# Kaiwa_vox_1_0.net
KiCad netlist of a schematic drawn in EAGLE
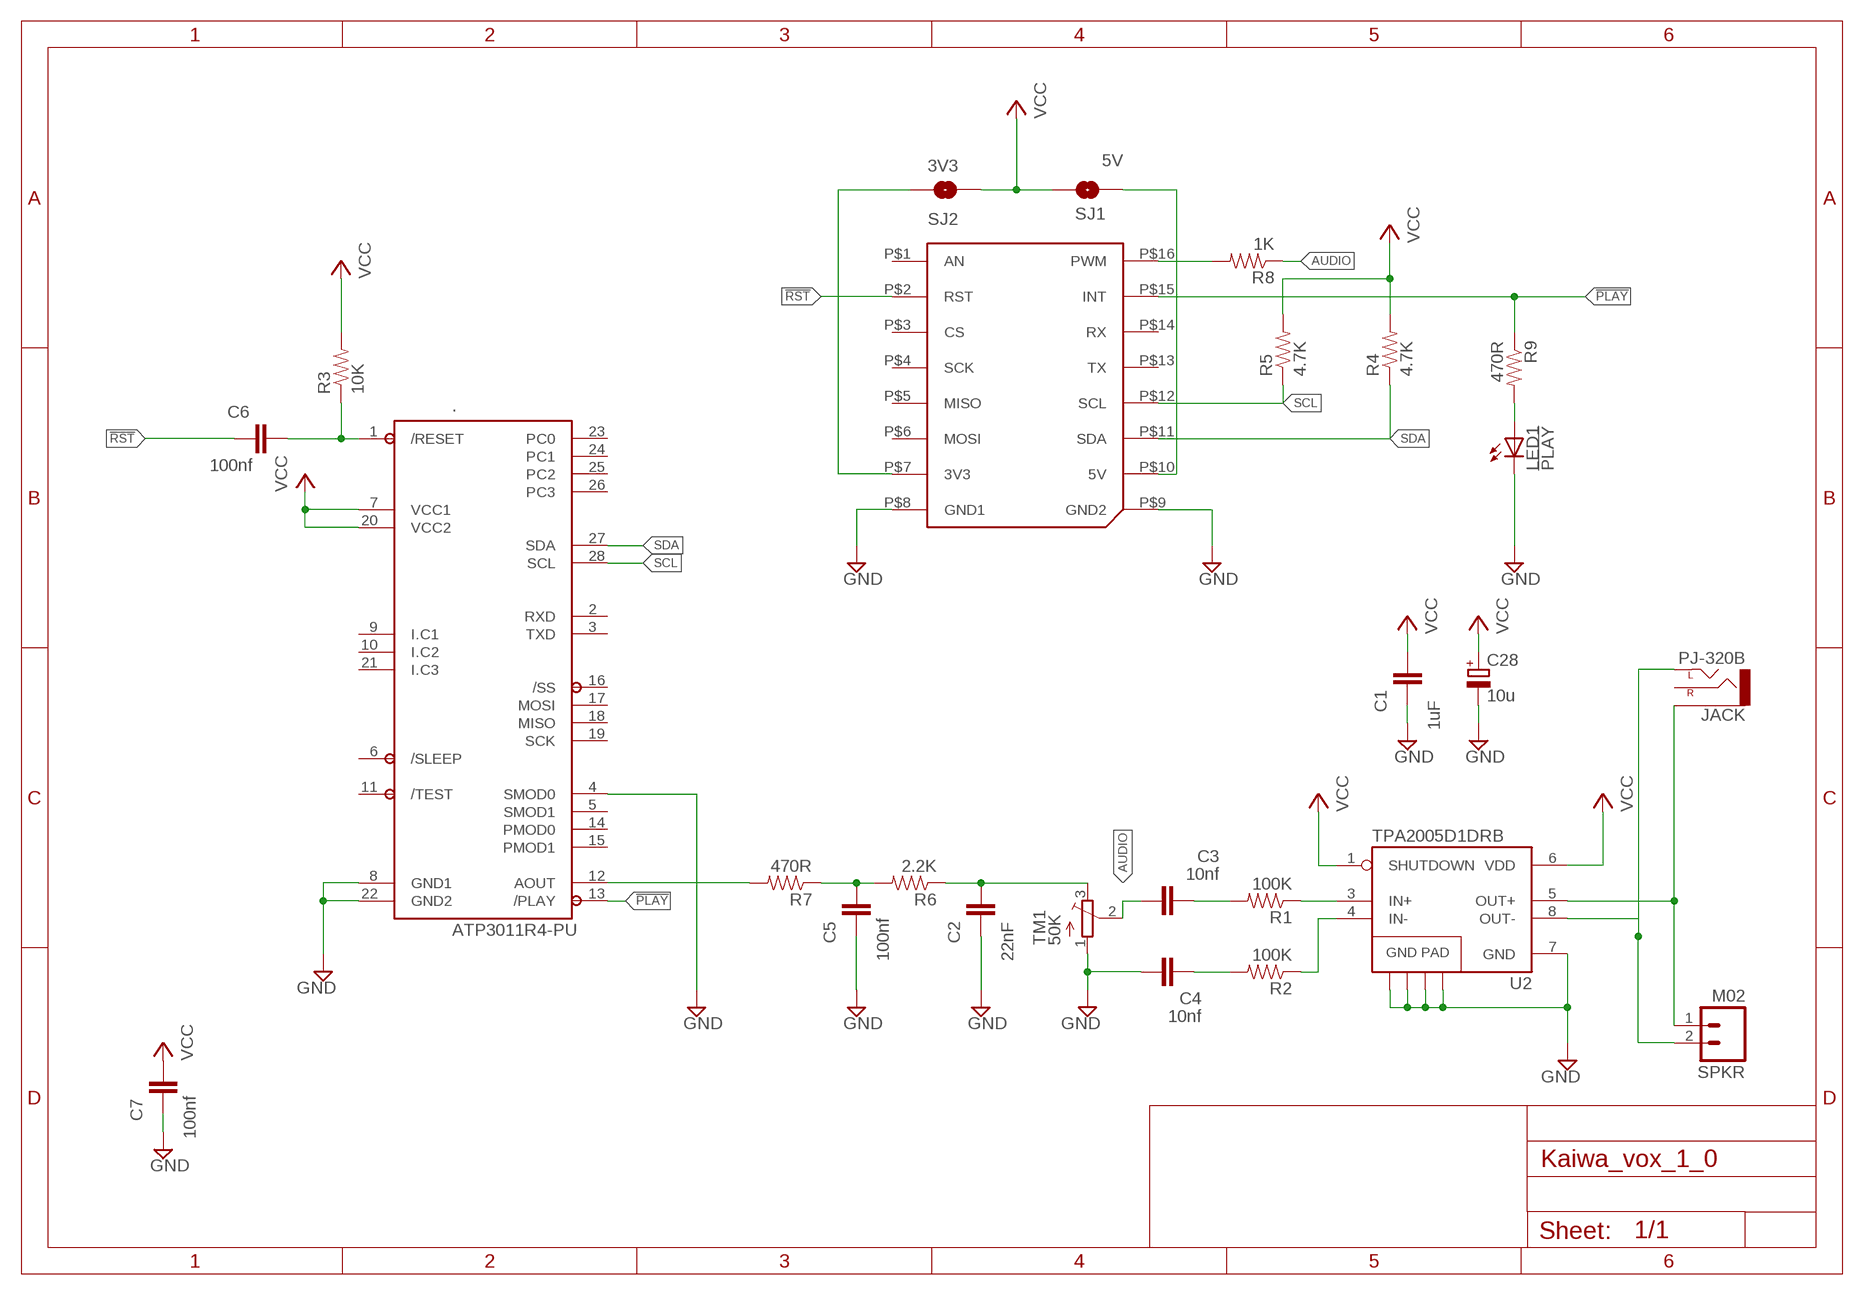
[diagram p0: schematic, sheet 1]

(export (version "E")
  (design (tool "Eeschema 10.0.6"))
  (components
    (comp (ref ".")
      (value "ATP3011R4-PU")
      (footprint "eagle-import:DIP28")
      (libsource (lib "eagle-import") (part "ATMEGA328"))
    )
    (comp (ref "C1")
      (value "1uF")
      (footprint "eagle-import:SPARKFUN_0805")
      (libsource (lib "eagle-import") (part "SPARKFUN_CAP0805"))
    )
    (comp (ref "C2")
      (value "22nF")
      (footprint "eagle-import:SPARKFUN_0805")
      (libsource (lib "eagle-import") (part "SPARKFUN_CAP0805"))
    )
    (comp (ref "C3")
      (value "10nf")
      (footprint "eagle-import:SPARKFUN_0805")
      (libsource (lib "eagle-import") (part "SPARKFUN_CAP0805"))
    )
    (comp (ref "C4")
      (value "10nf")
      (footprint "eagle-import:SPARKFUN_0805")
      (libsource (lib "eagle-import") (part "SPARKFUN_CAP0805"))
    )
    (comp (ref "C5")
      (value "100nf")
      (footprint "eagle-import:SPARKFUN_0805")
      (libsource (lib "eagle-import") (part "SPARKFUN_CAP0805"))
    )
    (comp (ref "C6")
      (value "100nf")
      (footprint "eagle-import:SPARKFUN_0805")
      (libsource (lib "eagle-import") (part "SPARKFUN_CAP0805"))
    )
    (comp (ref "C7")
      (value "100nf")
      (footprint "eagle-import:SPARKFUN_0805")
      (libsource (lib "eagle-import") (part "SPARKFUN_CAP0805"))
    )
    (comp (ref "C28")
      (value "10u")
      (footprint "eagle-import:A_3216-18R")
      (libsource (lib "eagle-import") (part "CPOL-EUA/3216-18R"))
    )
    (comp (ref "CLICK")
      (value "MIKROE_CLICKLARGE")
      (footprint "eagle-import:MIKROE_BUS_LARGE")
      (libsource (lib "eagle-import") (part "MIKROE_CLICKLARGE"))
    )
    (comp (ref "JACK")
      (value "PJ-320B")
      (footprint "eagle-import:FOOTPRINT")
      (libsource (lib "eagle-import") (part "PJ-320B"))
    )
    (comp (ref "LED1")
      (value "!PLAY")
      (footprint "eagle-import:SML0603")
      (libsource (lib "eagle-import") (part "LEDSML0603"))
    )
    (comp (ref "R1")
      (value "100K")
      (footprint "eagle-import:SPARKFUN_0805")
      (libsource (lib "eagle-import") (part "SPARKFUN_RESISTOR0805-RES"))
    )
    (comp (ref "R2")
      (value "100K")
      (footprint "eagle-import:SPARKFUN_0805")
      (libsource (lib "eagle-import") (part "SPARKFUN_RESISTOR0805-RES"))
    )
    (comp (ref "R3")
      (value "10K")
      (footprint "eagle-import:SPARKFUN_0805")
      (libsource (lib "eagle-import") (part "SPARKFUN_RESISTOR0805-RES"))
    )
    (comp (ref "R4")
      (value "4.7K")
      (footprint "eagle-import:SPARKFUN_0805")
      (libsource (lib "eagle-import") (part "SPARKFUN_RESISTOR0805-RES"))
    )
    (comp (ref "R5")
      (value "4.7K")
      (footprint "eagle-import:SPARKFUN_0805")
      (libsource (lib "eagle-import") (part "SPARKFUN_RESISTOR0805-RES"))
    )
    (comp (ref "R6")
      (value "2.2K")
      (footprint "eagle-import:SPARKFUN_0805")
      (libsource (lib "eagle-import") (part "SPARKFUN_RESISTOR0805-RES"))
    )
    (comp (ref "R7")
      (value "470R")
      (footprint "eagle-import:SPARKFUN_0805")
      (libsource (lib "eagle-import") (part "SPARKFUN_RESISTOR0805-RES"))
    )
    (comp (ref "R8")
      (value "1K")
      (footprint "eagle-import:SPARKFUN_0805")
      (libsource (lib "eagle-import") (part "SPARKFUN_RESISTOR0805-RES"))
    )
    (comp (ref "R9")
      (value "470R")
      (footprint "eagle-import:SPARKFUN_0805")
      (libsource (lib "eagle-import") (part "SPARKFUN_RESISTOR0805-RES"))
    )
    (comp (ref "SJ1")
      (value "5V")
      (footprint "eagle-import:SPARKFUN_SJ_2S-TRACE")
      (libsource (lib "eagle-import") (part "SPARKFUN_SOLDERJUMPERTRACE"))
    )
    (comp (ref "SJ2")
      (value "3V3")
      (footprint "eagle-import:SPARKFUN_SJ_2S-NO")
      (libsource (lib "eagle-import") (part "SPARKFUN_SOLDERJUMPERNO"))
    )
    (comp (ref "SPKR")
      (value "M02")
      (footprint "eagle-import:1X02_LOCK_LONGPADS")
      (libsource (lib "eagle-import") (part "M02LOCK_LONGPADS"))
    )
    (comp (ref "TM1")
      (value "50K")
      (footprint "eagle-import:TC33X")
      (libsource (lib "eagle-import") (part "TRIMPOTTC33X"))
    )
    (comp (ref "U2")
      (value "TPA2005D1DRB")
      (footprint "eagle-import:QFN-8_PAD")
      (libsource (lib "eagle-import") (part "TPA2005D1DRB"))
    )
  )
  (nets
    (net (code "1") (name "/~{PLAY}") (class "Default")
      (node (ref ".") (pin "13") (pinfunction "/PLAY_13") (pintype "bidirectional"))
      (node (ref "CLICK") (pin "P$15") (pinfunction "INT_P$15") (pintype "bidirectional"))
      (node (ref "R9") (pin "1") (pinfunction "1_1") (pintype "passive"))
    )
    (net (code "2") (name "/~{RST}") (class "Default")
      (node (ref "C6") (pin "2") (pinfunction "2_2") (pintype "passive"))
      (node (ref "CLICK") (pin "P$2") (pinfunction "RST_P$2") (pintype "bidirectional"))
    )
    (net (code "3") (name "AUDIO") (class "Default")
      (node (ref "C3") (pin "1") (pinfunction "1_1") (pintype "passive"))
      (node (ref "R8") (pin "1") (pinfunction "1_1") (pintype "passive"))
      (node (ref "TM1") (pin "2") (pinfunction "S_2") (pintype "passive"))
    )
    (net (code "4") (name "GND") (class "Default")
      (node (ref ".") (pin "22") (pinfunction "GND2_22") (pintype "bidirectional"))
      (node (ref ".") (pin "4") (pinfunction "SMOD0_4") (pintype "bidirectional"))
      (node (ref ".") (pin "8") (pinfunction "GND1_8") (pintype "bidirectional"))
      (node (ref "C1") (pin "2") (pinfunction "2_2") (pintype "passive"))
      (node (ref "C2") (pin "2") (pinfunction "2_2") (pintype "passive"))
      (node (ref "C28") (pin "-") (pinfunction "-_-") (pintype "passive"))
      (node (ref "C4") (pin "1") (pinfunction "1_1") (pintype "passive"))
      (node (ref "C5") (pin "2") (pinfunction "2_2") (pintype "passive"))
      (node (ref "C7") (pin "2") (pinfunction "2_2") (pintype "passive"))
      (node (ref "CLICK") (pin "P$8") (pinfunction "GND1_P$8") (pintype "bidirectional"))
      (node (ref "CLICK") (pin "P$9") (pinfunction "GND2_P$9") (pintype "bidirectional"))
      (node (ref "LED1") (pin "C") (pinfunction "C_C") (pintype "passive"))
      (node (ref "TM1") (pin "1") (pinfunction "A_1") (pintype "passive"))
      (node (ref "U2") (pin "10") (pinfunction "GND_10") (pintype "power_in"))
      (node (ref "U2") (pin "11") (pinfunction "GND_11") (pintype "power_in"))
      (node (ref "U2") (pin "12") (pinfunction "GND_12") (pintype "bidirectional"))
      (node (ref "U2") (pin "13") (pinfunction "GND_13") (pintype "bidirectional"))
      (node (ref "U2") (pin "7") (pinfunction "GND_7") (pintype "power_in"))
    )
    (net (code "5") (name "Net-(.-AOUT)") (class "Default")
      (node (ref ".") (pin "12") (pinfunction "AOUT_12") (pintype "bidirectional"))
      (node (ref "R7") (pin "2") (pinfunction "2_2") (pintype "passive"))
    )
    (net (code "6") (name "Net-(.-{slash}RESET)") (class "Default")
      (node (ref ".") (pin "1") (pinfunction "/RESET_1") (pintype "bidirectional"))
      (node (ref "C6") (pin "1") (pinfunction "1_1") (pintype "passive"))
      (node (ref "R3") (pin "1") (pinfunction "1_1") (pintype "passive"))
    )
    (net (code "7") (name "Net-(C3-Pad2)") (class "Default")
      (node (ref "C3") (pin "2") (pinfunction "2_2") (pintype "passive"))
      (node (ref "R1") (pin "2") (pinfunction "2_2") (pintype "passive"))
    )
    (net (code "8") (name "Net-(C4-Pad2)") (class "Default")
      (node (ref "C4") (pin "2") (pinfunction "2_2") (pintype "passive"))
      (node (ref "R2") (pin "2") (pinfunction "2_2") (pintype "passive"))
    )
    (net (code "9") (name "Net-(C5-Pad1)") (class "Default")
      (node (ref "C5") (pin "1") (pinfunction "1_1") (pintype "passive"))
      (node (ref "R6") (pin "2") (pinfunction "2_2") (pintype "passive"))
      (node (ref "R7") (pin "1") (pinfunction "1_1") (pintype "passive"))
    )
    (net (code "10") (name "Net-(CLICK-3V3)") (class "Default")
      (node (ref "CLICK") (pin "P$7") (pinfunction "3V3_P$7") (pintype "bidirectional"))
      (node (ref "SJ2") (pin "1") (pinfunction "1_1") (pintype "passive"))
    )
    (net (code "11") (name "Net-(CLICK-5V)") (class "Default")
      (node (ref "CLICK") (pin "P$10") (pinfunction "5V_P$10") (pintype "bidirectional"))
      (node (ref "SJ1") (pin "1") (pinfunction "1_1") (pintype "passive"))
    )
    (net (code "12") (name "Net-(CLICK-PWM)") (class "Default")
      (node (ref "CLICK") (pin "P$16") (pinfunction "PWM_P$16") (pintype "bidirectional"))
      (node (ref "R8") (pin "2") (pinfunction "2_2") (pintype "passive"))
    )
    (net (code "13") (name "Net-(JACK-LEFT)") (class "Default")
      (node (ref "JACK") (pin "2") (pinfunction "LEFT_2") (pintype "bidirectional"))
      (node (ref "SPKR") (pin "2") (pinfunction "2_2") (pintype "passive"))
      (node (ref "U2") (pin "8") (pinfunction "OUT-_8") (pintype "bidirectional"))
    )
    (net (code "14") (name "Net-(JACK-SLEEVE)") (class "Default")
      (node (ref "JACK") (pin "4") (pinfunction "SLEEVE_4") (pintype "bidirectional"))
      (node (ref "SPKR") (pin "1") (pinfunction "1_1") (pintype "passive"))
      (node (ref "U2") (pin "5") (pinfunction "OUT+_5") (pintype "bidirectional"))
    )
    (net (code "15") (name "Net-(LED1-PadA)") (class "Default")
      (node (ref "LED1") (pin "A") (pinfunction "A_A") (pintype "passive"))
      (node (ref "R9") (pin "2") (pinfunction "2_2") (pintype "passive"))
    )
    (net (code "16") (name "Net-(TM1-E)") (class "Default")
      (node (ref "C2") (pin "1") (pinfunction "1_1") (pintype "passive"))
      (node (ref "R6") (pin "1") (pinfunction "1_1") (pintype "passive"))
      (node (ref "TM1") (pin "3") (pinfunction "E_3") (pintype "passive"))
    )
    (net (code "17") (name "Net-(U2-IN+)") (class "Default")
      (node (ref "R1") (pin "1") (pinfunction "1_1") (pintype "passive"))
      (node (ref "U2") (pin "3") (pinfunction "IN+_3") (pintype "bidirectional"))
    )
    (net (code "18") (name "Net-(U2-IN-)") (class "Default")
      (node (ref "R2") (pin "1") (pinfunction "1_1") (pintype "passive"))
      (node (ref "U2") (pin "4") (pinfunction "IN-_4") (pintype "bidirectional"))
    )
    (net (code "19") (name "SCL") (class "Default")
      (node (ref ".") (pin "28") (pinfunction "SCL_28") (pintype "bidirectional"))
      (node (ref "CLICK") (pin "P$12") (pinfunction "SCL_P$12") (pintype "bidirectional"))
      (node (ref "R5") (pin "1") (pinfunction "1_1") (pintype "passive"))
    )
    (net (code "20") (name "SDA") (class "Default")
      (node (ref ".") (pin "27") (pinfunction "SDA_27") (pintype "bidirectional"))
      (node (ref "CLICK") (pin "P$11") (pinfunction "SDA_P$11") (pintype "bidirectional"))
      (node (ref "R4") (pin "1") (pinfunction "1_1") (pintype "passive"))
    )
    (net (code "21") (name "VCC") (class "Default")
      (node (ref ".") (pin "20") (pinfunction "VCC2_20") (pintype "bidirectional"))
      (node (ref ".") (pin "7") (pinfunction "VCC1_7") (pintype "bidirectional"))
      (node (ref "C1") (pin "1") (pinfunction "1_1") (pintype "passive"))
      (node (ref "C28") (pin "+") (pinfunction "+_+") (pintype "passive"))
      (node (ref "C7") (pin "1") (pinfunction "1_1") (pintype "passive"))
      (node (ref "R3") (pin "2") (pinfunction "2_2") (pintype "passive"))
      (node (ref "R4") (pin "2") (pinfunction "2_2") (pintype "passive"))
      (node (ref "R5") (pin "2") (pinfunction "2_2") (pintype "passive"))
      (node (ref "SJ1") (pin "2") (pinfunction "2_2") (pintype "passive"))
      (node (ref "SJ2") (pin "2") (pinfunction "2_2") (pintype "passive"))
      (node (ref "U2") (pin "1") (pinfunction "SHUTDOWN_1") (pintype "input"))
      (node (ref "U2") (pin "6") (pinfunction "VDD_6") (pintype "power_in"))
    )
    (net (code "22") (name "unconnected-(.-I.C1-Pad9)") (class "Default")
      (node (ref ".") (pin "9") (pinfunction "I.C1_9") (pintype "bidirectional"))
    )
    (net (code "23") (name "unconnected-(.-I.C2-Pad10)") (class "Default")
      (node (ref ".") (pin "10") (pinfunction "I.C2_10") (pintype "bidirectional"))
    )
    (net (code "24") (name "unconnected-(.-I.C3-Pad21)") (class "Default")
      (node (ref ".") (pin "21") (pinfunction "I.C3_21") (pintype "bidirectional"))
    )
    (net (code "25") (name "unconnected-(.-MISO-Pad18)") (class "Default")
      (node (ref ".") (pin "18") (pinfunction "MISO_18") (pintype "bidirectional"))
    )
    (net (code "26") (name "unconnected-(.-MOSI-Pad17)") (class "Default")
      (node (ref ".") (pin "17") (pinfunction "MOSI_17") (pintype "bidirectional"))
    )
    (net (code "27") (name "unconnected-(.-PC0-Pad23)") (class "Default")
      (node (ref ".") (pin "23") (pinfunction "PC0_23") (pintype "bidirectional"))
    )
    (net (code "28") (name "unconnected-(.-PC1-Pad24)") (class "Default")
      (node (ref ".") (pin "24") (pinfunction "PC1_24") (pintype "bidirectional"))
    )
    (net (code "29") (name "unconnected-(.-PC2-Pad25)") (class "Default")
      (node (ref ".") (pin "25") (pinfunction "PC2_25") (pintype "bidirectional"))
    )
    (net (code "30") (name "unconnected-(.-PC3-Pad26)") (class "Default")
      (node (ref ".") (pin "26") (pinfunction "PC3_26") (pintype "bidirectional"))
    )
    (net (code "31") (name "unconnected-(.-PMOD0-Pad14)") (class "Default")
      (node (ref ".") (pin "14") (pinfunction "PMOD0_14") (pintype "bidirectional"))
    )
    (net (code "32") (name "unconnected-(.-PMOD1-Pad15)") (class "Default")
      (node (ref ".") (pin "15") (pinfunction "PMOD1_15") (pintype "bidirectional"))
    )
    (net (code "33") (name "unconnected-(.-RXD-Pad2)") (class "Default")
      (node (ref ".") (pin "2") (pinfunction "RXD_2") (pintype "bidirectional"))
    )
    (net (code "34") (name "unconnected-(.-SCK-Pad19)") (class "Default")
      (node (ref ".") (pin "19") (pinfunction "SCK_19") (pintype "bidirectional"))
    )
    (net (code "35") (name "unconnected-(.-SMOD1-Pad5)") (class "Default")
      (node (ref ".") (pin "5") (pinfunction "SMOD1_5") (pintype "bidirectional"))
    )
    (net (code "36") (name "unconnected-(.-TXD-Pad3)") (class "Default")
      (node (ref ".") (pin "3") (pinfunction "TXD_3") (pintype "bidirectional"))
    )
    (net (code "37") (name "unconnected-(.-{slash}SLEEP-Pad6)") (class "Default")
      (node (ref ".") (pin "6") (pinfunction "/SLEEP_6") (pintype "bidirectional"))
    )
    (net (code "38") (name "unconnected-(.-{slash}SS-Pad16)") (class "Default")
      (node (ref ".") (pin "16") (pinfunction "/SS_16") (pintype "bidirectional"))
    )
    (net (code "39") (name "unconnected-(.-{slash}TEST-Pad11)") (class "Default")
      (node (ref ".") (pin "11") (pinfunction "/TEST_11") (pintype "bidirectional"))
    )
    (net (code "40") (name "unconnected-(CLICK-AN-PadP$1)") (class "Default")
      (node (ref "CLICK") (pin "P$1") (pinfunction "AN_P$1") (pintype "bidirectional"))
    )
    (net (code "41") (name "unconnected-(CLICK-CS-PadP$3)") (class "Default")
      (node (ref "CLICK") (pin "P$3") (pinfunction "CS_P$3") (pintype "bidirectional"))
    )
    (net (code "42") (name "unconnected-(CLICK-MISO-PadP$5)") (class "Default")
      (node (ref "CLICK") (pin "P$5") (pinfunction "MISO_P$5") (pintype "bidirectional"))
    )
    (net (code "43") (name "unconnected-(CLICK-MOSI-PadP$6)") (class "Default")
      (node (ref "CLICK") (pin "P$6") (pinfunction "MOSI_P$6") (pintype "bidirectional"))
    )
    (net (code "44") (name "unconnected-(CLICK-RX-PadP$14)") (class "Default")
      (node (ref "CLICK") (pin "P$14") (pinfunction "RX_P$14") (pintype "bidirectional"))
    )
    (net (code "45") (name "unconnected-(CLICK-SCK-PadP$4)") (class "Default")
      (node (ref "CLICK") (pin "P$4") (pinfunction "SCK_P$4") (pintype "bidirectional"))
    )
    (net (code "46") (name "unconnected-(CLICK-TX-PadP$13)") (class "Default")
      (node (ref "CLICK") (pin "P$13") (pinfunction "TX_P$13") (pintype "bidirectional"))
    )
    (net (code "47") (name "unconnected-(JACK-RIGHT-Pad3)") (class "Default")
      (node (ref "JACK") (pin "3") (pinfunction "RIGHT_3") (pintype "bidirectional"))
    )
  )
)
